# Robot_Dog_Boston_V1.net
KiCad netlist of a schematic drawn in EAGLE
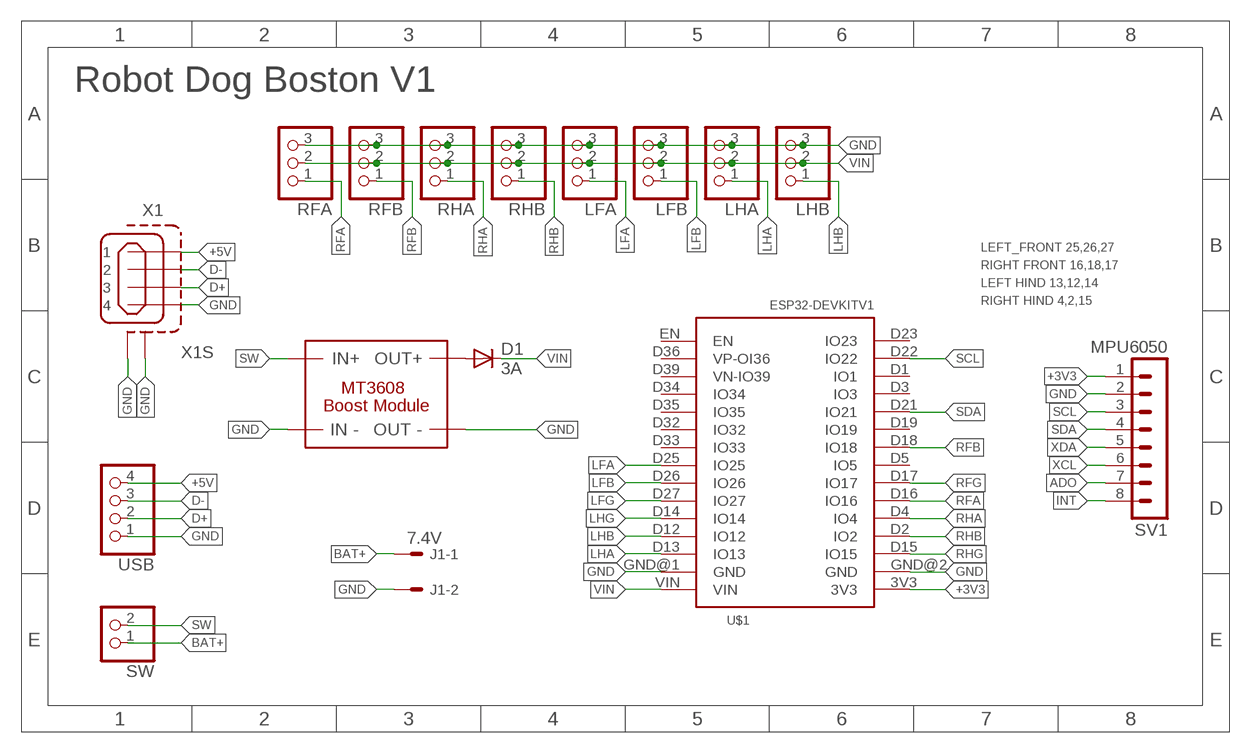
[diagram p0: schematic, sheet 1]

(export (version "E")
  (design (tool "Eeschema 10.0.6"))
  (components
    (comp (ref "D1")
      (value "3A")
      (footprint "eagle-import:DO15-12")
      (libsource (lib "eagle-import") (part "1N5060GP"))
    )
    (comp (ref "J1")
      (value "7.4V")
      (footprint "eagle-import:7395-02")
      (libsource (lib "eagle-import") (part "22-?-0205-7028"))
    )
    (comp (ref "LFA")
      (value "PINHD-1X3")
      (footprint "eagle-import:1X03")
      (libsource (lib "eagle-import") (part "PINHD-1X3"))
    )
    (comp (ref "LFB")
      (value "PINHD-1X3")
      (footprint "eagle-import:1X03")
      (libsource (lib "eagle-import") (part "PINHD-1X3"))
    )
    (comp (ref "LHA")
      (value "PINHD-1X3")
      (footprint "eagle-import:1X03")
      (libsource (lib "eagle-import") (part "PINHD-1X3"))
    )
    (comp (ref "LHB")
      (value "PINHD-1X3")
      (footprint "eagle-import:1X03")
      (libsource (lib "eagle-import") (part "PINHD-1X3"))
    )
    (comp (ref "RFA")
      (value "PINHD-1X3")
      (footprint "eagle-import:1X03")
      (libsource (lib "eagle-import") (part "PINHD-1X3"))
    )
    (comp (ref "RFB")
      (value "PINHD-1X3")
      (footprint "eagle-import:1X03")
      (libsource (lib "eagle-import") (part "PINHD-1X3"))
    )
    (comp (ref "RHA")
      (value "PINHD-1X3")
      (footprint "eagle-import:1X03")
      (libsource (lib "eagle-import") (part "PINHD-1X3"))
    )
    (comp (ref "RHB")
      (value "PINHD-1X3")
      (footprint "eagle-import:1X03")
      (libsource (lib "eagle-import") (part "PINHD-1X3"))
    )
    (comp (ref "SV1")
      (value "MPU6050")
      (footprint "eagle-import:MA08-1")
      (libsource (lib "eagle-import") (part "MA08-1"))
    )
    (comp (ref "SW")
      (value "PINHD-1X2")
      (footprint "eagle-import:1X02")
      (libsource (lib "eagle-import") (part "PINHD-1X2"))
    )
    (comp (ref "U$1")
      (value "ESP32DEVKITV1S")
      (footprint "eagle-import:ESP32-DEVKIT1S")
      (libsource (lib "eagle-import") (part "ESP32DEVKITV1S"))
    )
    (comp (ref "U$2")
      (value "REGULATOR_MICRO15.4X9.4")
      (footprint "eagle-import:5V_REGULATOR_BOARD_MICRO_15_4_X_9_4")
      (libsource (lib "eagle-import") (part "REGULATOR_MICRO15.4X9.4"))
    )
    (comp (ref "USB")
      (value "PINHD-1X4/90")
      (footprint "eagle-import:1X04_90")
      (libsource (lib "eagle-import") (part "PINHD-1X4/90"))
    )
    (comp (ref "X1")
      (value "MINI-USB_SHIELD4P-85-32004-00X")
      (footprint "eagle-import:85-32004-00X")
      (libsource (lib "eagle-import") (part "MINI-USB_SHIELD4P-85-32004-00X"))
    )
  )
  (nets
    (net (code "1") (name "+3V3") (class "Default")
      (node (ref "SV1") (pin "1") (pinfunction "1_1") (pintype "passive"))
      (node (ref "U$1") (pin "3V3") (pinfunction "3V3_3V3") (pintype "bidirectional"))
    )
    (net (code "2") (name "+5V") (class "Default")
      (node (ref "USB") (pin "4") (pinfunction "4_4") (pintype "passive"))
      (node (ref "X1") (pin "1") (pinfunction "1_1") (pintype "passive"))
    )
    (net (code "3") (name "ADO") (class "Default")
      (node (ref "SV1") (pin "7") (pinfunction "7_7") (pintype "passive"))
    )
    (net (code "4") (name "BAT+") (class "Default")
      (node (ref "J1") (pin "1") (pinfunction "S_1") (pintype "passive"))
      (node (ref "SW") (pin "1") (pinfunction "1_1") (pintype "passive"))
    )
    (net (code "5") (name "D+") (class "Default")
      (node (ref "USB") (pin "2") (pinfunction "2_2") (pintype "passive"))
      (node (ref "X1") (pin "3") (pinfunction "3_3") (pintype "passive"))
    )
    (net (code "6") (name "D-") (class "Default")
      (node (ref "USB") (pin "3") (pinfunction "3_3") (pintype "passive"))
      (node (ref "X1") (pin "2") (pinfunction "2_2") (pintype "passive"))
    )
    (net (code "7") (name "GND") (class "Default")
      (node (ref "J1") (pin "2") (pinfunction "S_2") (pintype "passive"))
      (node (ref "LFA") (pin "3") (pinfunction "3_3") (pintype "passive"))
      (node (ref "LFB") (pin "3") (pinfunction "3_3") (pintype "passive"))
      (node (ref "LHA") (pin "3") (pinfunction "3_3") (pintype "passive"))
      (node (ref "LHB") (pin "3") (pinfunction "3_3") (pintype "passive"))
      (node (ref "RFA") (pin "3") (pinfunction "3_3") (pintype "passive"))
      (node (ref "RFB") (pin "3") (pinfunction "3_3") (pintype "passive"))
      (node (ref "RHA") (pin "3") (pinfunction "3_3") (pintype "passive"))
      (node (ref "RHB") (pin "3") (pinfunction "3_3") (pintype "passive"))
      (node (ref "SV1") (pin "2") (pinfunction "2_2") (pintype "passive"))
      (node (ref "U$1") (pin "GND@1") (pinfunction "GND_GND@1") (pintype "bidirectional"))
      (node (ref "U$1") (pin "GND@2") (pinfunction "GND_GND@2") (pintype "bidirectional"))
      (node (ref "U$2") (pin "IN-") (pinfunction "IN-_IN-") (pintype "bidirectional"))
      (node (ref "U$2") (pin "OUT-") (pinfunction "OUT-_OUT-") (pintype "bidirectional"))
      (node (ref "USB") (pin "1") (pinfunction "1_1") (pintype "passive"))
      (node (ref "X1") (pin "4") (pinfunction "4_4") (pintype "passive"))
      (node (ref "X1") (pin "M1") (pinfunction "S1_M1") (pintype "passive"))
      (node (ref "X1") (pin "M2") (pinfunction "S2_M2") (pintype "passive"))
    )
    (net (code "8") (name "INT") (class "Default")
      (node (ref "SV1") (pin "8") (pinfunction "8_8") (pintype "passive"))
    )
    (net (code "9") (name "LFA") (class "Default")
      (node (ref "LFA") (pin "1") (pinfunction "1_1") (pintype "passive"))
      (node (ref "U$1") (pin "D25") (pinfunction "IO25_D25") (pintype "bidirectional"))
    )
    (net (code "10") (name "LFB") (class "Default")
      (node (ref "LFB") (pin "1") (pinfunction "1_1") (pintype "passive"))
      (node (ref "U$1") (pin "D26") (pinfunction "IO26_D26") (pintype "bidirectional"))
    )
    (net (code "11") (name "LFG") (class "Default")
      (node (ref "U$1") (pin "D27") (pinfunction "IO27_D27") (pintype "bidirectional"))
    )
    (net (code "12") (name "LHA") (class "Default")
      (node (ref "LHA") (pin "1") (pinfunction "1_1") (pintype "passive"))
      (node (ref "U$1") (pin "D13") (pinfunction "IO13_D13") (pintype "bidirectional"))
    )
    (net (code "13") (name "LHB") (class "Default")
      (node (ref "LHB") (pin "1") (pinfunction "1_1") (pintype "passive"))
      (node (ref "U$1") (pin "D12") (pinfunction "IO12_D12") (pintype "bidirectional"))
    )
    (net (code "14") (name "LHG") (class "Default")
      (node (ref "U$1") (pin "D14") (pinfunction "IO14_D14") (pintype "bidirectional"))
    )
    (net (code "15") (name "Net-(D1-PadA)") (class "Default")
      (node (ref "D1") (pin "A") (pinfunction "A_A") (pintype "passive"))
      (node (ref "U$2") (pin "OUT+") (pinfunction "OUT+_OUT+") (pintype "bidirectional"))
    )
    (net (code "16") (name "RFA") (class "Default")
      (node (ref "RFA") (pin "1") (pinfunction "1_1") (pintype "passive"))
      (node (ref "U$1") (pin "D16") (pinfunction "IO16_D16") (pintype "bidirectional"))
    )
    (net (code "17") (name "RFB") (class "Default")
      (node (ref "RFB") (pin "1") (pinfunction "1_1") (pintype "passive"))
      (node (ref "U$1") (pin "D18") (pinfunction "IO18_D18") (pintype "bidirectional"))
    )
    (net (code "18") (name "RFG") (class "Default")
      (node (ref "U$1") (pin "D17") (pinfunction "IO17_D17") (pintype "bidirectional"))
    )
    (net (code "19") (name "RHA") (class "Default")
      (node (ref "RHA") (pin "1") (pinfunction "1_1") (pintype "passive"))
      (node (ref "U$1") (pin "D4") (pinfunction "IO4_D4") (pintype "bidirectional"))
    )
    (net (code "20") (name "RHB") (class "Default")
      (node (ref "RHB") (pin "1") (pinfunction "1_1") (pintype "passive"))
      (node (ref "U$1") (pin "D2") (pinfunction "IO2_D2") (pintype "bidirectional"))
    )
    (net (code "21") (name "RHG") (class "Default")
      (node (ref "U$1") (pin "D15") (pinfunction "IO15_D15") (pintype "bidirectional"))
    )
    (net (code "22") (name "SCL") (class "Default")
      (node (ref "SV1") (pin "3") (pinfunction "3_3") (pintype "passive"))
      (node (ref "U$1") (pin "D22") (pinfunction "IO22_D22") (pintype "bidirectional"))
    )
    (net (code "23") (name "SDA") (class "Default")
      (node (ref "SV1") (pin "4") (pinfunction "4_4") (pintype "passive"))
      (node (ref "U$1") (pin "D21") (pinfunction "IO21_D21") (pintype "bidirectional"))
    )
    (net (code "24") (name "SW") (class "Default")
      (node (ref "SW") (pin "2") (pinfunction "2_2") (pintype "passive"))
      (node (ref "U$2") (pin "IN+") (pinfunction "IN+_IN+") (pintype "bidirectional"))
    )
    (net (code "25") (name "VIN") (class "Default")
      (node (ref "D1") (pin "C") (pinfunction "C_C") (pintype "passive"))
      (node (ref "LFA") (pin "2") (pinfunction "2_2") (pintype "passive"))
      (node (ref "LFB") (pin "2") (pinfunction "2_2") (pintype "passive"))
      (node (ref "LHA") (pin "2") (pinfunction "2_2") (pintype "passive"))
      (node (ref "LHB") (pin "2") (pinfunction "2_2") (pintype "passive"))
      (node (ref "RFA") (pin "2") (pinfunction "2_2") (pintype "passive"))
      (node (ref "RFB") (pin "2") (pinfunction "2_2") (pintype "passive"))
      (node (ref "RHA") (pin "2") (pinfunction "2_2") (pintype "passive"))
      (node (ref "RHB") (pin "2") (pinfunction "2_2") (pintype "passive"))
      (node (ref "U$1") (pin "VIN") (pinfunction "VIN_VIN") (pintype "bidirectional"))
    )
    (net (code "26") (name "XCL") (class "Default")
      (node (ref "SV1") (pin "6") (pinfunction "6_6") (pintype "passive"))
    )
    (net (code "27") (name "XDA") (class "Default")
      (node (ref "SV1") (pin "5") (pinfunction "5_5") (pintype "passive"))
    )
    (net (code "28") (name "unconnected-(U$1-IO1-PadD1)") (class "Default")
      (node (ref "U$1") (pin "D1") (pinfunction "IO1_D1") (pintype "bidirectional"))
    )
    (net (code "29") (name "unconnected-(U$1-IO3-PadD3)") (class "Default")
      (node (ref "U$1") (pin "D3") (pinfunction "IO3_D3") (pintype "bidirectional"))
    )
    (net (code "30") (name "unconnected-(U$1-IO5-PadD5)") (class "Default")
      (node (ref "U$1") (pin "D5") (pinfunction "IO5_D5") (pintype "bidirectional"))
    )
    (net (code "31") (name "unconnected-(U$1-IO19-PadD19)") (class "Default")
      (node (ref "U$1") (pin "D19") (pinfunction "IO19_D19") (pintype "bidirectional"))
    )
    (net (code "32") (name "unconnected-(U$1-IO23-PadD23)") (class "Default")
      (node (ref "U$1") (pin "D23") (pinfunction "IO23_D23") (pintype "bidirectional"))
    )
    (net (code "33") (name "unconnected-(U$1-IO32-PadD32)") (class "Default")
      (node (ref "U$1") (pin "D32") (pinfunction "IO32_D32") (pintype "bidirectional"))
    )
    (net (code "34") (name "unconnected-(U$1-IO33-PadD33)") (class "Default")
      (node (ref "U$1") (pin "D33") (pinfunction "IO33_D33") (pintype "bidirectional"))
    )
    (net (code "35") (name "unconnected-(U$1-IO34-PadD34)") (class "Default")
      (node (ref "U$1") (pin "D34") (pinfunction "IO34_D34") (pintype "bidirectional"))
    )
    (net (code "36") (name "unconnected-(U$1-IO35-PadD35)") (class "Default")
      (node (ref "U$1") (pin "D35") (pinfunction "IO35_D35") (pintype "bidirectional"))
    )
    (net (code "37") (name "unconnected-(U$1-PadEN)") (class "Default")
      (node (ref "U$1") (pin "EN") (pinfunction "EN_EN") (pintype "bidirectional"))
    )
    (net (code "38") (name "unconnected-(U$1-VN-IO39-PadD39)") (class "Default")
      (node (ref "U$1") (pin "D39") (pinfunction "VN-IO39_D39") (pintype "bidirectional"))
    )
    (net (code "39") (name "unconnected-(U$1-VP-OI36-PadD36)") (class "Default")
      (node (ref "U$1") (pin "D36") (pinfunction "VP-OI36_D36") (pintype "bidirectional"))
    )
  )
)
